# Input.net
KiCad netlist of a schematic drawn in Altium Designer
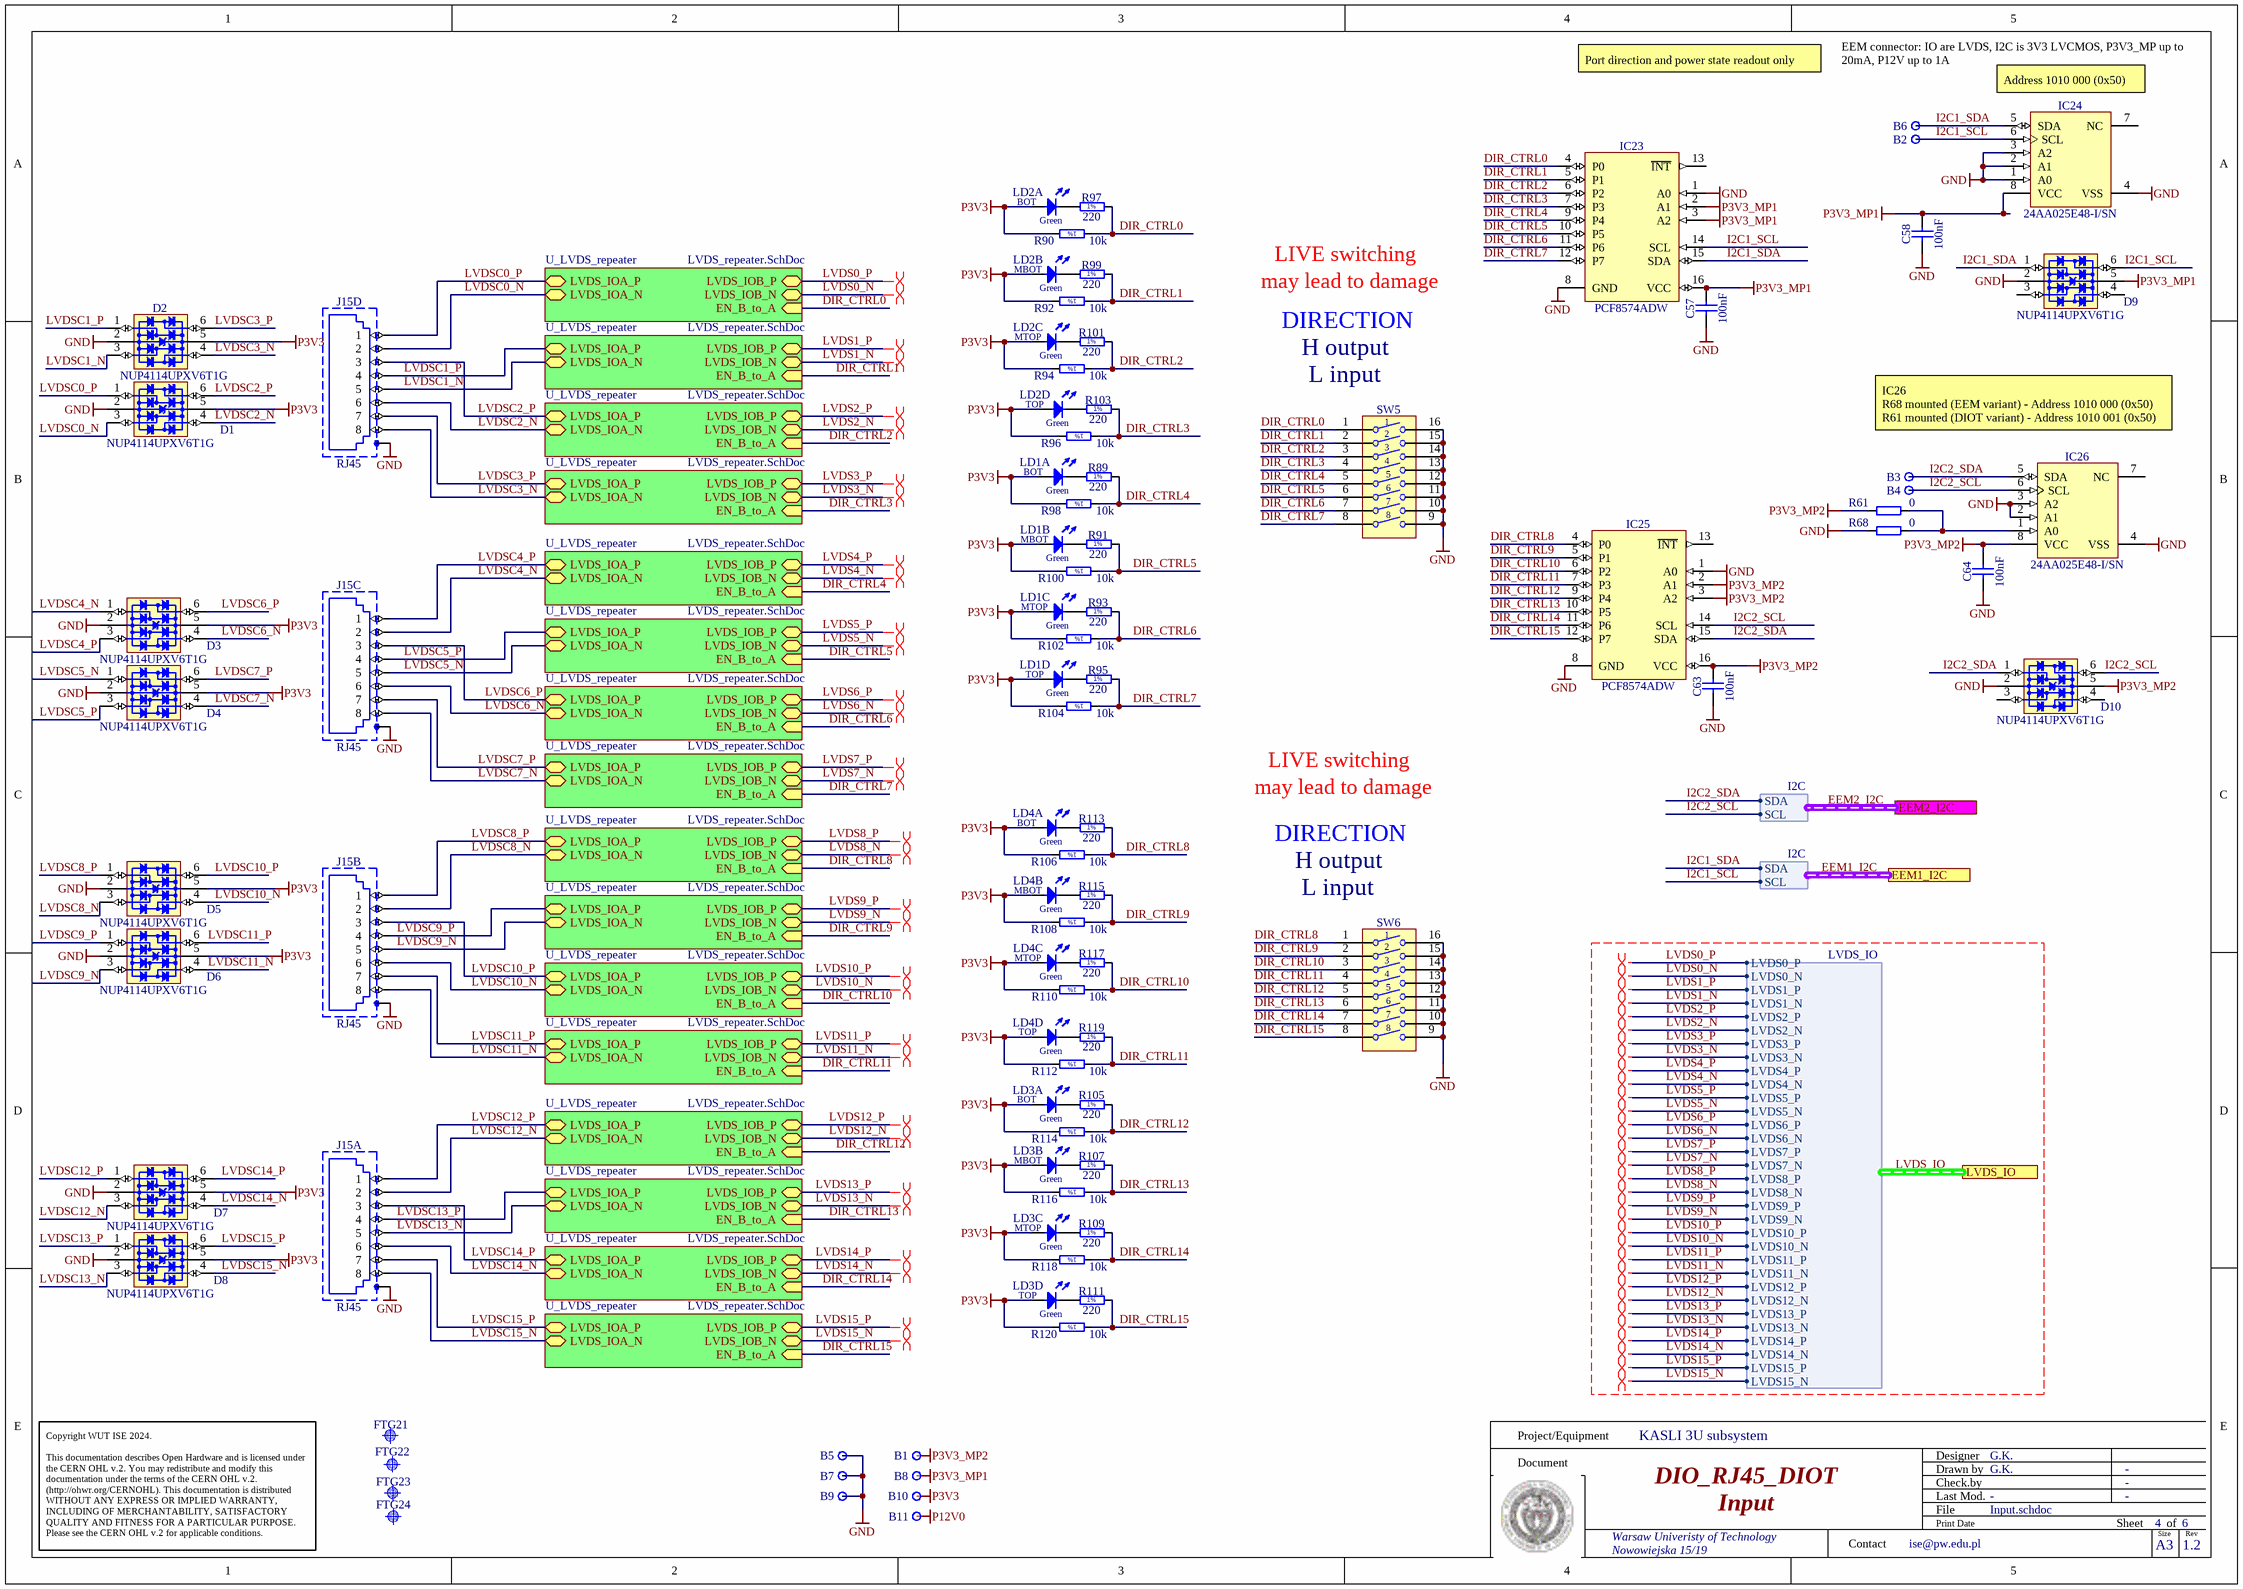
[diagram p0: Input.schdoc]

(export (version "E")
  (design (tool "Eeschema 10.0.6"))
  (components
    (comp (ref "B1")
      (value "Plated Hole")
      (footprint "c130h60")
      (description "Single Terminal Socket")
      (fields (field (name "PART NUMBER") "PLATED_HOLE0.6_PAD1.3") (field (name "AUTHOR") "CERN DEM MR"))
      (libsource (lib "Eletro-mechanical") (part "Single Terminal Socket"))
    )
    (comp (ref "B2")
      (value "Plated Hole")
      (footprint "c130h60")
      (description "Single Terminal Socket")
      (fields (field (name "PART NUMBER") "PLATED_HOLE0.6_PAD1.3") (field (name "AUTHOR") "CERN DEM MR"))
      (libsource (lib "Eletro-mechanical") (part "Single Terminal Socket"))
    )
    (comp (ref "B3")
      (value "Plated Hole")
      (footprint "c130h60")
      (description "Single Terminal Socket")
      (fields (field (name "PART NUMBER") "PLATED_HOLE0.6_PAD1.3") (field (name "AUTHOR") "CERN DEM MR"))
      (libsource (lib "Eletro-mechanical") (part "Single Terminal Socket"))
    )
    (comp (ref "B4")
      (value "Plated Hole")
      (footprint "c130h60")
      (description "Single Terminal Socket")
      (fields (field (name "PART NUMBER") "PLATED_HOLE0.6_PAD1.3") (field (name "AUTHOR") "CERN DEM MR"))
      (libsource (lib "Eletro-mechanical") (part "Single Terminal Socket"))
    )
    (comp (ref "B5")
      (value "Plated Hole")
      (footprint "c130h60")
      (description "Single Terminal Socket")
      (fields (field (name "PART NUMBER") "PLATED_HOLE0.6_PAD1.3") (field (name "AUTHOR") "CERN DEM MR"))
      (libsource (lib "Eletro-mechanical") (part "Single Terminal Socket"))
    )
    (comp (ref "B6")
      (value "Plated Hole")
      (footprint "c130h60")
      (description "Single Terminal Socket")
      (fields (field (name "PART NUMBER") "PLATED_HOLE0.6_PAD1.3") (field (name "AUTHOR") "CERN DEM MR"))
      (libsource (lib "Eletro-mechanical") (part "Single Terminal Socket"))
    )
    (comp (ref "B7")
      (value "Plated Hole")
      (footprint "c130h60")
      (description "Single Terminal Socket")
      (fields (field (name "PART NUMBER") "PLATED_HOLE0.6_PAD1.3") (field (name "AUTHOR") "CERN DEM MR"))
      (libsource (lib "Eletro-mechanical") (part "Single Terminal Socket"))
    )
    (comp (ref "B8")
      (value "Plated Hole")
      (footprint "c130h60")
      (description "Single Terminal Socket")
      (fields (field (name "PART NUMBER") "PLATED_HOLE0.6_PAD1.3") (field (name "AUTHOR") "CERN DEM MR"))
      (libsource (lib "Eletro-mechanical") (part "Single Terminal Socket"))
    )
    (comp (ref "B9")
      (value "Plated Hole")
      (footprint "c130h60")
      (description "Single Terminal Socket")
      (fields (field (name "PART NUMBER") "PLATED_HOLE0.6_PAD1.3") (field (name "AUTHOR") "CERN DEM MR"))
      (libsource (lib "Eletro-mechanical") (part "Single Terminal Socket"))
    )
    (comp (ref "B10")
      (value "Plated Hole")
      (footprint "c130h60")
      (description "Single Terminal Socket")
      (fields (field (name "PART NUMBER") "PLATED_HOLE0.6_PAD1.3") (field (name "AUTHOR") "CERN DEM MR"))
      (libsource (lib "Eletro-mechanical") (part "Single Terminal Socket"))
    )
    (comp (ref "B11")
      (value "Plated Hole")
      (footprint "c130h60")
      (description "Single Terminal Socket")
      (fields (field (name "PART NUMBER") "PLATED_HOLE0.6_PAD1.3") (field (name "AUTHOR") "CERN DEM MR"))
      (libsource (lib "Eletro-mechanical") (part "Single Terminal Socket"))
    )
    (comp (ref "C57")
      (value "100nF")
      (footprint "CAPC1005X55N")
      (description "Non-polarised capacitor")
      (fields
        (field (name "PART NUMBER") "CC0402_100NF_16V_10%_X5R")
        (field (name "VOLTAGE") "16V")
        (field (name "AUTHOR") "CERN DEM JLC")
      )
      (libsource (lib "Capacitors") (part "Capacitor - non polarized"))
    )
    (comp (ref "C58")
      (value "100nF")
      (footprint "CAPC1005X55N")
      (description "Non-polarised capacitor")
      (fields
        (field (name "PART NUMBER") "CC0402_100NF_16V_10%_X5R")
        (field (name "VOLTAGE") "16V")
        (field (name "AUTHOR") "CERN DEM JLC")
      )
      (libsource (lib "Capacitors") (part "Capacitor - non polarized"))
    )
    (comp (ref "C63")
      (value "100nF")
      (footprint "CAPC1005X55N")
      (description "Non-polarised capacitor")
      (fields
        (field (name "PART NUMBER") "CC0402_100NF_16V_10%_X5R")
        (field (name "VOLTAGE") "16V")
        (field (name "AUTHOR") "CERN DEM JLC")
      )
      (libsource (lib "Capacitors") (part "Capacitor - non polarized"))
    )
    (comp (ref "C64")
      (value "100nF")
      (footprint "CAPC1005X55N")
      (description "Non-polarised capacitor")
      (fields
        (field (name "PART NUMBER") "CC0402_100NF_16V_10%_X5R")
        (field (name "VOLTAGE") "16V")
        (field (name "AUTHOR") "CERN DEM JLC")
      )
      (libsource (lib "Capacitors") (part "Capacitor - non polarized"))
    )
    (comp (ref "D1")
      (value "NUP4114UPXV6T1G")
      (footprint "SOTFL50P160X60-6N")
      (fields
        (field (name "VOLTAGE") "5.5V")
        (field (name "MANUFACTURER") "ON SEMICONDUCTOR")
        (field (name "AUTHOR") "CERN DEM JLC")
      )
      (libsource (lib "ICs And Semiconductors") (part "NUP4114"))
    )
    (comp (ref "D2")
      (value "NUP4114UPXV6T1G")
      (footprint "SOTFL50P160X60-6N")
      (fields
        (field (name "VOLTAGE") "5.5V")
        (field (name "MANUFACTURER") "ON SEMICONDUCTOR")
        (field (name "AUTHOR") "CERN DEM JLC")
      )
      (libsource (lib "ICs And Semiconductors") (part "NUP4114"))
    )
    (comp (ref "D3")
      (value "NUP4114UPXV6T1G")
      (footprint "SOTFL50P160X60-6N")
      (fields
        (field (name "VOLTAGE") "5.5V")
        (field (name "MANUFACTURER") "ON SEMICONDUCTOR")
        (field (name "AUTHOR") "CERN DEM JLC")
      )
      (libsource (lib "ICs And Semiconductors") (part "NUP4114"))
    )
    (comp (ref "D4")
      (value "NUP4114UPXV6T1G")
      (footprint "SOTFL50P160X60-6N")
      (fields
        (field (name "VOLTAGE") "5.5V")
        (field (name "MANUFACTURER") "ON SEMICONDUCTOR")
        (field (name "AUTHOR") "CERN DEM JLC")
      )
      (libsource (lib "ICs And Semiconductors") (part "NUP4114"))
    )
    (comp (ref "D5")
      (value "NUP4114UPXV6T1G")
      (footprint "SOTFL50P160X60-6N")
      (fields
        (field (name "VOLTAGE") "5.5V")
        (field (name "MANUFACTURER") "ON SEMICONDUCTOR")
        (field (name "AUTHOR") "CERN DEM JLC")
      )
      (libsource (lib "ICs And Semiconductors") (part "NUP4114"))
    )
    (comp (ref "D6")
      (value "NUP4114UPXV6T1G")
      (footprint "SOTFL50P160X60-6N")
      (fields
        (field (name "VOLTAGE") "5.5V")
        (field (name "MANUFACTURER") "ON SEMICONDUCTOR")
        (field (name "AUTHOR") "CERN DEM JLC")
      )
      (libsource (lib "ICs And Semiconductors") (part "NUP4114"))
    )
    (comp (ref "D7")
      (value "NUP4114UPXV6T1G")
      (footprint "SOTFL50P160X60-6N")
      (fields
        (field (name "VOLTAGE") "5.5V")
        (field (name "MANUFACTURER") "ON SEMICONDUCTOR")
        (field (name "AUTHOR") "CERN DEM JLC")
      )
      (libsource (lib "ICs And Semiconductors") (part "NUP4114"))
    )
    (comp (ref "D8")
      (value "NUP4114UPXV6T1G")
      (footprint "SOTFL50P160X60-6N")
      (fields
        (field (name "VOLTAGE") "5.5V")
        (field (name "MANUFACTURER") "ON SEMICONDUCTOR")
        (field (name "AUTHOR") "CERN DEM JLC")
      )
      (libsource (lib "ICs And Semiconductors") (part "NUP4114"))
    )
    (comp (ref "D9")
      (value "NUP4114UPXV6T1G")
      (footprint "SOTFL50P160X60-6N")
      (fields
        (field (name "VOLTAGE") "5.5V")
        (field (name "MANUFACTURER") "ON SEMICONDUCTOR")
        (field (name "AUTHOR") "CERN DEM JLC")
      )
      (libsource (lib "ICs And Semiconductors") (part "NUP4114"))
    )
    (comp (ref "D10")
      (value "NUP4114UPXV6T1G")
      (footprint "SOTFL50P160X60-6N")
      (fields
        (field (name "VOLTAGE") "5.5V")
        (field (name "MANUFACTURER") "ON SEMICONDUCTOR")
        (field (name "AUTHOR") "CERN DEM JLC")
      )
      (libsource (lib "ICs And Semiconductors") (part "NUP4114"))
    )
    (comp (ref "FTG21")
      (value "Use only in PCB")
      (footprint "FIDUCIAL_TOP_C100-200")
      (description "Fiducial Target")
      (fields (field (name "PART NUMBER") "FIDUCIAL_TARGET_C100-200") (field (name "AUTHOR") "CERN DEM JLC"))
      (libsource (lib "Eletro-mechanical") (part "Fiducial Target"))
    )
    (comp (ref "FTG22")
      (value "Use only in PCB")
      (footprint "FIDUCIAL_TOP_S100-200")
      (description "Fiducial Target")
      (fields (field (name "PART NUMBER") "FIDUCIAL_TARGET_S100-200") (field (name "AUTHOR") "CERN DEM JLC"))
      (libsource (lib "Eletro-mechanical") (part "Fiducial Target"))
    )
    (comp (ref "FTG23")
      (value "Use only in PCB")
      (footprint "FIDUCIAL_TOP_S200-400")
      (description "Fiducial Target")
      (fields (field (name "PART NUMBER") "FIDUCIAL_TARGET_S200-400") (field (name "AUTHOR") "CERN DEM JLC"))
      (libsource (lib "Eletro-mechanical") (part "Fiducial Target"))
    )
    (comp (ref "FTG24")
      (value "Use only in PCB")
      (footprint "FIDUCIAL_TOP_S100-200")
      (description "Fiducial Target")
      (fields (field (name "PART NUMBER") "FIDUCIAL_TARGET_S100-200") (field (name "AUTHOR") "CERN DEM JLC"))
      (libsource (lib "Eletro-mechanical") (part "Fiducial Target"))
    )
    (comp (ref "IC23")
      (value "PCF8574ADW")
      (footprint "SOIC127P1030X265-16N")
      (description "Remote 8-bit I/O Expander For I2C Bus")
      (fields (field (name "MANUFACTURER") "TEXAS INSTRUMENTS") (field (name "AUTHOR") "CERN DEM JLC"))
      (libsource (lib "ICs And Semiconductors") (part "PCF8574ADW"))
    )
    (comp (ref "IC24")
      (value "24AA025E48-I/SN")
      (footprint "SOIC127P600X175-8N")
      (description "1.7V-5.5V, 2K I2C™ Serial EEPROMs with EUI-48™ Node Identity")
      (fields (field (name "MANUFACTURER") "MICROCHIP TECHNOLOGY") (field (name "AUTHOR") "CERN DEM MR"))
      (libsource (lib "ICs And Semiconductors") (part "24AA025E48-I/SN"))
    )
    (comp (ref "IC25")
      (value "PCF8574ADW")
      (footprint "SOIC127P1030X265-16N")
      (description "Remote 8-bit I/O Expander For I2C Bus")
      (fields (field (name "MANUFACTURER") "TEXAS INSTRUMENTS") (field (name "AUTHOR") "CERN DEM JLC"))
      (libsource (lib "ICs And Semiconductors") (part "PCF8574ADW"))
    )
    (comp (ref "IC26")
      (value "24AA025E48-I/SN")
      (footprint "SOIC127P600X175-8N")
      (description "1.7V-5.5V, 2K I2C™ Serial EEPROMs with EUI-48™ Node Identity")
      (fields (field (name "MANUFACTURER") "MICROCHIP TECHNOLOGY") (field (name "AUTHOR") "CERN DEM MR"))
      (libsource (lib "ICs And Semiconductors") (part "24AA025E48-I/SN"))
    )
    (comp (ref "J15")
      (value "RJ45")
      (footprint "TYCO_5406203-3")
      (description "Connector 4 x RJ45 + Shield")
      (fields
        (field (name "PART NUMBER") "TYCO_5406203-3")
        (field (name "MANUFACTURER") "TYCO ELECTRONICS")
        (field (name "AUTHOR") "CERN DEM JLC")
      )
      (libsource (lib "Connectors") (part "Connector 4 x RJ45 + Shield"))
    )
    (comp (ref "LD1")
      (value "Green")
      (footprint "LED_BIVAR_H485CGDL")
      (description "LED x4 Green 1C2A-BOT_3C4A_5C6A_7C8A-TOP")
      (fields
        (field (name "PART NUMBER") "LED_BIVAR_H485CGDL")
        (field (name "MANUFACTURER") "BIVAR")
        (field (name "AUTHOR") "CERN DEM JLC")
      )
      (libsource (lib "ICs And Semiconductors") (part "LED x4 Green 1C2A-BOT_3C4A_5C6A_7C8A-TOP"))
    )
    (comp (ref "LD2")
      (value "Green")
      (footprint "LED_BIVAR_H485CGDL")
      (description "LED x4 Green 1C2A-BOT_3C4A_5C6A_7C8A-TOP")
      (fields
        (field (name "PART NUMBER") "LED_BIVAR_H485CGDL")
        (field (name "MANUFACTURER") "BIVAR")
        (field (name "AUTHOR") "CERN DEM JLC")
      )
      (libsource (lib "ICs And Semiconductors") (part "LED x4 Green 1C2A-BOT_3C4A_5C6A_7C8A-TOP"))
    )
    (comp (ref "LD3")
      (value "Green")
      (footprint "LED_BIVAR_H485CGDL")
      (description "LED x4 Green 1C2A-BOT_3C4A_5C6A_7C8A-TOP")
      (fields
        (field (name "PART NUMBER") "LED_BIVAR_H485CGDL")
        (field (name "MANUFACTURER") "BIVAR")
        (field (name "AUTHOR") "CERN DEM JLC")
      )
      (libsource (lib "ICs And Semiconductors") (part "LED x4 Green 1C2A-BOT_3C4A_5C6A_7C8A-TOP"))
    )
    (comp (ref "LD4")
      (value "Green")
      (footprint "LED_BIVAR_H485CGDL")
      (description "LED x4 Green 1C2A-BOT_3C4A_5C6A_7C8A-TOP")
      (fields
        (field (name "PART NUMBER") "LED_BIVAR_H485CGDL")
        (field (name "MANUFACTURER") "BIVAR")
        (field (name "AUTHOR") "CERN DEM JLC")
      )
      (libsource (lib "ICs And Semiconductors") (part "LED x4 Green 1C2A-BOT_3C4A_5C6A_7C8A-TOP"))
    )
    (comp (ref "R61")
      (value "0")
      (footprint "RESC1005X35N")
      (description "Resistor")
      (fields
        (field (name "PART NUMBER") "R0402_0R_JUMPER")
        (field (name "MANUFACTURER") "GENERIC")
        (field (name "AUTHOR") "CERN DEM JLC")
      )
      (libsource (lib "Resistors") (part "Resistor"))
    )
    (comp (ref "R68")
      (value "0")
      (footprint "RESC1005X35N")
      (description "Resistor")
      (fields
        (field (name "PART NUMBER") "R0402_0R_JUMPER")
        (field (name "MANUFACTURER") "GENERIC")
        (field (name "AUTHOR") "CERN DEM JLC")
      )
      (libsource (lib "Resistors") (part "Resistor"))
    )
    (comp (ref "R89")
      (value "220")
      (footprint "RESC1608X55N")
      (description "Resistor - 1%")
      (fields
        (field (name "PART NUMBER") "R0603_220R_1%_0.1W_100PPM")
        (field (name "POWER") "0.1W")
        (field (name "AUTHOR") "CERN DEM JLC")
      )
      (libsource (lib "Resistors") (part "Resistor - 1%"))
    )
    (comp (ref "R90")
      (value "10k")
      (footprint "RESC1005X40N")
      (description "Resistor - 1%")
      (fields
        (field (name "PART NUMBER") "R0402_10K_1%_0.0625W_100PPM")
        (field (name "POWER") "0.0625W")
        (field (name "AUTHOR") "CERN DEM JLC")
      )
      (libsource (lib "Resistors") (part "Resistor - 1%"))
    )
    (comp (ref "R91")
      (value "220")
      (footprint "RESC1608X55N")
      (description "Resistor - 1%")
      (fields
        (field (name "PART NUMBER") "R0603_220R_1%_0.1W_100PPM")
        (field (name "POWER") "0.1W")
        (field (name "AUTHOR") "CERN DEM JLC")
      )
      (libsource (lib "Resistors") (part "Resistor - 1%"))
    )
    (comp (ref "R92")
      (value "10k")
      (footprint "RESC1005X40N")
      (description "Resistor - 1%")
      (fields
        (field (name "PART NUMBER") "R0402_10K_1%_0.0625W_100PPM")
        (field (name "POWER") "0.0625W")
        (field (name "AUTHOR") "CERN DEM JLC")
      )
      (libsource (lib "Resistors") (part "Resistor - 1%"))
    )
    (comp (ref "R93")
      (value "220")
      (footprint "RESC1608X55N")
      (description "Resistor - 1%")
      (fields
        (field (name "PART NUMBER") "R0603_220R_1%_0.1W_100PPM")
        (field (name "POWER") "0.1W")
        (field (name "AUTHOR") "CERN DEM JLC")
      )
      (libsource (lib "Resistors") (part "Resistor - 1%"))
    )
    (comp (ref "R94")
      (value "10k")
      (footprint "RESC1005X40N")
      (description "Resistor - 1%")
      (fields
        (field (name "PART NUMBER") "R0402_10K_1%_0.0625W_100PPM")
        (field (name "POWER") "0.0625W")
        (field (name "AUTHOR") "CERN DEM JLC")
      )
      (libsource (lib "Resistors") (part "Resistor - 1%"))
    )
    (comp (ref "R95")
      (value "220")
      (footprint "RESC1608X55N")
      (description "Resistor - 1%")
      (fields
        (field (name "PART NUMBER") "R0603_220R_1%_0.1W_100PPM")
        (field (name "POWER") "0.1W")
        (field (name "AUTHOR") "CERN DEM JLC")
      )
      (libsource (lib "Resistors") (part "Resistor - 1%"))
    )
    (comp (ref "R96")
      (value "10k")
      (footprint "RESC1005X40N")
      (description "Resistor - 1%")
      (fields
        (field (name "PART NUMBER") "R0402_10K_1%_0.0625W_100PPM")
        (field (name "POWER") "0.0625W")
        (field (name "AUTHOR") "CERN DEM JLC")
      )
      (libsource (lib "Resistors") (part "Resistor - 1%"))
    )
    (comp (ref "R97")
      (value "220")
      (footprint "RESC1608X55N")
      (description "Resistor - 1%")
      (fields
        (field (name "PART NUMBER") "R0603_220R_1%_0.1W_100PPM")
        (field (name "POWER") "0.1W")
        (field (name "AUTHOR") "CERN DEM JLC")
      )
      (libsource (lib "Resistors") (part "Resistor - 1%"))
    )
    (comp (ref "R98")
      (value "10k")
      (footprint "RESC1005X40N")
      (description "Resistor - 1%")
      (fields
        (field (name "PART NUMBER") "R0402_10K_1%_0.0625W_100PPM")
        (field (name "POWER") "0.0625W")
        (field (name "AUTHOR") "CERN DEM JLC")
      )
      (libsource (lib "Resistors") (part "Resistor - 1%"))
    )
    (comp (ref "R99")
      (value "220")
      (footprint "RESC1608X55N")
      (description "Resistor - 1%")
      (fields
        (field (name "PART NUMBER") "R0603_220R_1%_0.1W_100PPM")
        (field (name "POWER") "0.1W")
        (field (name "AUTHOR") "CERN DEM JLC")
      )
      (libsource (lib "Resistors") (part "Resistor - 1%"))
    )
    (comp (ref "R100")
      (value "10k")
      (footprint "RESC1005X40N")
      (description "Resistor - 1%")
      (fields
        (field (name "PART NUMBER") "R0402_10K_1%_0.0625W_100PPM")
        (field (name "POWER") "0.0625W")
        (field (name "AUTHOR") "CERN DEM JLC")
      )
      (libsource (lib "Resistors") (part "Resistor - 1%"))
    )
    (comp (ref "R101")
      (value "220")
      (footprint "RESC1608X55N")
      (description "Resistor - 1%")
      (fields
        (field (name "PART NUMBER") "R0603_220R_1%_0.1W_100PPM")
        (field (name "POWER") "0.1W")
        (field (name "AUTHOR") "CERN DEM JLC")
      )
      (libsource (lib "Resistors") (part "Resistor - 1%"))
    )
    (comp (ref "R102")
      (value "10k")
      (footprint "RESC1005X40N")
      (description "Resistor - 1%")
      (fields
        (field (name "PART NUMBER") "R0402_10K_1%_0.0625W_100PPM")
        (field (name "POWER") "0.0625W")
        (field (name "AUTHOR") "CERN DEM JLC")
      )
      (libsource (lib "Resistors") (part "Resistor - 1%"))
    )
    (comp (ref "R103")
      (value "220")
      (footprint "RESC1608X55N")
      (description "Resistor - 1%")
      (fields
        (field (name "PART NUMBER") "R0603_220R_1%_0.1W_100PPM")
        (field (name "POWER") "0.1W")
        (field (name "AUTHOR") "CERN DEM JLC")
      )
      (libsource (lib "Resistors") (part "Resistor - 1%"))
    )
    (comp (ref "R104")
      (value "10k")
      (footprint "RESC1005X40N")
      (description "Resistor - 1%")
      (fields
        (field (name "PART NUMBER") "R0402_10K_1%_0.0625W_100PPM")
        (field (name "POWER") "0.0625W")
        (field (name "AUTHOR") "CERN DEM JLC")
      )
      (libsource (lib "Resistors") (part "Resistor - 1%"))
    )
    (comp (ref "R105")
      (value "220")
      (footprint "RESC1608X55N")
      (description "Resistor - 1%")
      (fields
        (field (name "PART NUMBER") "R0603_220R_1%_0.1W_100PPM")
        (field (name "POWER") "0.1W")
        (field (name "AUTHOR") "CERN DEM JLC")
      )
      (libsource (lib "Resistors") (part "Resistor - 1%"))
    )
    (comp (ref "R106")
      (value "10k")
      (footprint "RESC1005X40N")
      (description "Resistor - 1%")
      (fields
        (field (name "PART NUMBER") "R0402_10K_1%_0.0625W_100PPM")
        (field (name "POWER") "0.0625W")
        (field (name "AUTHOR") "CERN DEM JLC")
      )
      (libsource (lib "Resistors") (part "Resistor - 1%"))
    )
    (comp (ref "R107")
      (value "220")
      (footprint "RESC1608X55N")
      (description "Resistor - 1%")
      (fields
        (field (name "PART NUMBER") "R0603_220R_1%_0.1W_100PPM")
        (field (name "POWER") "0.1W")
        (field (name "AUTHOR") "CERN DEM JLC")
      )
      (libsource (lib "Resistors") (part "Resistor - 1%"))
    )
    (comp (ref "R108")
      (value "10k")
      (footprint "RESC1005X40N")
      (description "Resistor - 1%")
      (fields
        (field (name "PART NUMBER") "R0402_10K_1%_0.0625W_100PPM")
        (field (name "POWER") "0.0625W")
        (field (name "AUTHOR") "CERN DEM JLC")
      )
      (libsource (lib "Resistors") (part "Resistor - 1%"))
    )
    (comp (ref "R109")
      (value "220")
      (footprint "RESC1608X55N")
      (description "Resistor - 1%")
      (fields
        (field (name "PART NUMBER") "R0603_220R_1%_0.1W_100PPM")
        (field (name "POWER") "0.1W")
        (field (name "AUTHOR") "CERN DEM JLC")
      )
      (libsource (lib "Resistors") (part "Resistor - 1%"))
    )
    (comp (ref "R110")
      (value "10k")
      (footprint "RESC1005X40N")
      (description "Resistor - 1%")
      (fields
        (field (name "PART NUMBER") "R0402_10K_1%_0.0625W_100PPM")
        (field (name "POWER") "0.0625W")
        (field (name "AUTHOR") "CERN DEM JLC")
      )
      (libsource (lib "Resistors") (part "Resistor - 1%"))
    )
    (comp (ref "R111")
      (value "220")
      (footprint "RESC1608X55N")
      (description "Resistor - 1%")
      (fields
        (field (name "PART NUMBER") "R0603_220R_1%_0.1W_100PPM")
        (field (name "POWER") "0.1W")
        (field (name "AUTHOR") "CERN DEM JLC")
      )
      (libsource (lib "Resistors") (part "Resistor - 1%"))
    )
    (comp (ref "R112")
      (value "10k")
      (footprint "RESC1005X40N")
      (description "Resistor - 1%")
      (fields
        (field (name "PART NUMBER") "R0402_10K_1%_0.0625W_100PPM")
        (field (name "POWER") "0.0625W")
        (field (name "AUTHOR") "CERN DEM JLC")
      )
      (libsource (lib "Resistors") (part "Resistor - 1%"))
    )
    (comp (ref "R113")
      (value "220")
      (footprint "RESC1608X55N")
      (description "Resistor - 1%")
      (fields
        (field (name "PART NUMBER") "R0603_220R_1%_0.1W_100PPM")
        (field (name "POWER") "0.1W")
        (field (name "AUTHOR") "CERN DEM JLC")
      )
      (libsource (lib "Resistors") (part "Resistor - 1%"))
    )
    (comp (ref "R114")
      (value "10k")
      (footprint "RESC1005X40N")
      (description "Resistor - 1%")
      (fields
        (field (name "PART NUMBER") "R0402_10K_1%_0.0625W_100PPM")
        (field (name "POWER") "0.0625W")
        (field (name "AUTHOR") "CERN DEM JLC")
      )
      (libsource (lib "Resistors") (part "Resistor - 1%"))
    )
    (comp (ref "R115")
      (value "220")
      (footprint "RESC1608X55N")
      (description "Resistor - 1%")
      (fields
        (field (name "PART NUMBER") "R0603_220R_1%_0.1W_100PPM")
        (field (name "POWER") "0.1W")
        (field (name "AUTHOR") "CERN DEM JLC")
      )
      (libsource (lib "Resistors") (part "Resistor - 1%"))
    )
    (comp (ref "R116")
      (value "10k")
      (footprint "RESC1005X40N")
      (description "Resistor - 1%")
      (fields
        (field (name "PART NUMBER") "R0402_10K_1%_0.0625W_100PPM")
        (field (name "POWER") "0.0625W")
        (field (name "AUTHOR") "CERN DEM JLC")
      )
      (libsource (lib "Resistors") (part "Resistor - 1%"))
    )
    (comp (ref "R117")
      (value "220")
      (footprint "RESC1608X55N")
      (description "Resistor - 1%")
      (fields
        (field (name "PART NUMBER") "R0603_220R_1%_0.1W_100PPM")
        (field (name "POWER") "0.1W")
        (field (name "AUTHOR") "CERN DEM JLC")
      )
      (libsource (lib "Resistors") (part "Resistor - 1%"))
    )
    (comp (ref "R118")
      (value "10k")
      (footprint "RESC1005X40N")
      (description "Resistor - 1%")
      (fields
        (field (name "PART NUMBER") "R0402_10K_1%_0.0625W_100PPM")
        (field (name "POWER") "0.0625W")
        (field (name "AUTHOR") "CERN DEM JLC")
      )
      (libsource (lib "Resistors") (part "Resistor - 1%"))
    )
    (comp (ref "R119")
      (value "220")
      (footprint "RESC1608X55N")
      (description "Resistor - 1%")
      (fields
        (field (name "PART NUMBER") "R0603_220R_1%_0.1W_100PPM")
        (field (name "POWER") "0.1W")
        (field (name "AUTHOR") "CERN DEM JLC")
      )
      (libsource (lib "Resistors") (part "Resistor - 1%"))
    )
    (comp (ref "R120")
      (value "10k")
      (footprint "RESC1005X40N")
      (description "Resistor - 1%")
      (fields
        (field (name "PART NUMBER") "R0402_10K_1%_0.0625W_100PPM")
        (field (name "POWER") "0.0625W")
        (field (name "AUTHOR") "CERN DEM JLC")
      )
      (libsource (lib "Resistors") (part "Resistor - 1%"))
    )
    (comp (ref "SW5")
      (value "Switch")
      (footprint "SW_TYCO_1-1571983-0")
      (description "8 Ways SPST DIP Switch")
      (fields
        (field (name "PART NUMBER") "SW_TYCO_1-1571983-0")
        (field (name "MANUFACTURER") "TYCO")
        (field (name "AUTHOR") "CERN DEM JLC")
      )
      (libsource (lib "Eletro-mechanical") (part "SW 8x SPST DIP Switch"))
    )
    (comp (ref "SW6")
      (value "Switch")
      (footprint "SW_TYCO_1-1571983-0")
      (description "8 Ways SPST DIP Switch")
      (fields
        (field (name "PART NUMBER") "SW_TYCO_1-1571983-0")
        (field (name "MANUFACTURER") "TYCO")
        (field (name "AUTHOR") "CERN DEM JLC")
      )
      (libsource (lib "Eletro-mechanical") (part "SW 8x SPST DIP Switch"))
    )
  )
  (nets
    (net (code "4") (name "/DIR_CTRL0") (class "Default")
      (node (ref "IC23") (pin "4") (pinfunction "P0_4") (pintype "bidirectional"))
      (node (ref "R90") (pin "1") (pinfunction "1_1") (pintype "passive"))
      (node (ref "R97") (pin "2") (pinfunction "2_2") (pintype "passive"))
      (node (ref "SW5") (pin "1") (pinfunction "1_1") (pintype "passive"))
    )
    (net (code "5") (name "/DIR_CTRL1") (class "Default")
      (node (ref "IC23") (pin "5") (pinfunction "P1_5") (pintype "bidirectional"))
      (node (ref "R92") (pin "1") (pinfunction "1_1") (pintype "passive"))
      (node (ref "R99") (pin "2") (pinfunction "2_2") (pintype "passive"))
      (node (ref "SW5") (pin "2") (pinfunction "2_2") (pintype "passive"))
    )
    (net (code "6") (name "/DIR_CTRL2") (class "Default")
      (node (ref "IC23") (pin "6") (pinfunction "P2_6") (pintype "bidirectional"))
      (node (ref "R101") (pin "2") (pinfunction "2_2") (pintype "passive"))
      (node (ref "R94") (pin "1") (pinfunction "1_1") (pintype "passive"))
      (node (ref "SW5") (pin "3") (pinfunction "3_3") (pintype "passive"))
    )
    (net (code "7") (name "/DIR_CTRL3") (class "Default")
      (node (ref "IC23") (pin "7") (pinfunction "P3_7") (pintype "bidirectional"))
      (node (ref "R103") (pin "2") (pinfunction "2_2") (pintype "passive"))
      (node (ref "R96") (pin "1") (pinfunction "1_1") (pintype "passive"))
      (node (ref "SW5") (pin "4") (pinfunction "4_4") (pintype "passive"))
    )
    (net (code "8") (name "/DIR_CTRL4") (class "Default")
      (node (ref "IC23") (pin "9") (pinfunction "P4_9") (pintype "bidirectional"))
      (node (ref "R89") (pin "2") (pinfunction "2_2") (pintype "passive"))
      (node (ref "R98") (pin "1") (pinfunction "1_1") (pintype "passive"))
      (node (ref "SW5") (pin "5") (pinfunction "5_5") (pintype "passive"))
    )
    (net (code "9") (name "/DIR_CTRL5") (class "Default")
      (node (ref "IC23") (pin "10") (pinfunction "P5_10") (pintype "bidirectional"))
      (node (ref "R100") (pin "1") (pinfunction "1_1") (pintype "passive"))
      (node (ref "R91") (pin "2") (pinfunction "2_2") (pintype "passive"))
      (node (ref "SW5") (pin "6") (pinfunction "6_6") (pintype "passive"))
    )
    (net (code "10") (name "/DIR_CTRL6") (class "Default")
      (node (ref "IC23") (pin "11") (pinfunction "P6_11") (pintype "bidirectional"))
      (node (ref "R102") (pin "1") (pinfunction "1_1") (pintype "passive"))
      (node (ref "R93") (pin "2") (pinfunction "2_2") (pintype "passive"))
      (node (ref "SW5") (pin "7") (pinfunction "7_7") (pintype "passive"))
    )
    (net (code "11") (name "/DIR_CTRL7") (class "Default")
      (node (ref "IC23") (pin "12") (pinfunction "P7_12") (pintype "bidirectional"))
      (node (ref "R104") (pin "1") (pinfunction "1_1") (pintype "passive"))
      (node (ref "R95") (pin "2") (pinfunction "2_2") (pintype "passive"))
      (node (ref "SW5") (pin "8") (pinfunction "8_8") (pintype "passive"))
    )
    (net (code "12") (name "/DIR_CTRL8") (class "Default")
      (node (ref "IC25") (pin "4") (pinfunction "P0_4") (pintype "bidirectional"))
      (node (ref "R106") (pin "1") (pinfunction "1_1") (pintype "passive"))
      (node (ref "R113") (pin "2") (pinfunction "2_2") (pintype "passive"))
      (node (ref "SW6") (pin "1") (pinfunction "1_1") (pintype "passive"))
    )
    (net (code "13") (name "/DIR_CTRL9") (class "Default")
      (node (ref "IC25") (pin "5") (pinfunction "P1_5") (pintype "bidirectional"))
      (node (ref "R108") (pin "1") (pinfunction "1_1") (pintype "passive"))
      (node (ref "R115") (pin "2") (pinfunction "2_2") (pintype "passive"))
      (node (ref "SW6") (pin "2") (pinfunction "2_2") (pintype "passive"))
    )
    (net (code "14") (name "/DIR_CTRL10") (class "Default")
      (node (ref "IC25") (pin "6") (pinfunction "P2_6") (pintype "bidirectional"))
      (node (ref "R110") (pin "1") (pinfunction "1_1") (pintype "passive"))
      (node (ref "R117") (pin "2") (pinfunction "2_2") (pintype "passive"))
      (node (ref "SW6") (pin "3") (pinfunction "3_3") (pintype "passive"))
    )
    (net (code "15") (name "/DIR_CTRL11") (class "Default")
      (node (ref "IC25") (pin "7") (pinfunction "P3_7") (pintype "bidirectional"))
      (node (ref "R112") (pin "1") (pinfunction "1_1") (pintype "passive"))
      (node (ref "R119") (pin "2") (pinfunction "2_2") (pintype "passive"))
      (node (ref "SW6") (pin "4") (pinfunction "4_4") (pintype "passive"))
    )
    (net (code "16") (name "/DIR_CTRL12") (class "Default")
      (node (ref "IC25") (pin "9") (pinfunction "P4_9") (pintype "bidirectional"))
      (node (ref "R105") (pin "2") (pinfunction "2_2") (pintype "passive"))
      (node (ref "R114") (pin "1") (pinfunction "1_1") (pintype "passive"))
      (node (ref "SW6") (pin "5") (pinfunction "5_5") (pintype "passive"))
    )
    (net (code "17") (name "/DIR_CTRL13") (class "Default")
      (node (ref "IC25") (pin "10") (pinfunction "P5_10") (pintype "bidirectional"))
      (node (ref "R107") (pin "2") (pinfunction "2_2") (pintype "passive"))
      (node (ref "R116") (pin "1") (pinfunction "1_1") (pintype "passive"))
      (node (ref "SW6") (pin "6") (pinfunction "6_6") (pintype "passive"))
    )
    (net (code "18") (name "/DIR_CTRL14") (class "Default")
      (node (ref "IC25") (pin "11") (pinfunction "P6_11") (pintype "bidirectional"))
      (node (ref "R109") (pin "2") (pinfunction "2_2") (pintype "passive"))
      (node (ref "R118") (pin "1") (pinfunction "1_1") (pintype "passive"))
      (node (ref "SW6") (pin "7") (pinfunction "7_7") (pintype "passive"))
    )
    (net (code "19") (name "/DIR_CTRL15") (class "Default")
      (node (ref "IC25") (pin "12") (pinfunction "P7_12") (pintype "bidirectional"))
      (node (ref "R111") (pin "2") (pinfunction "2_2") (pintype "passive"))
      (node (ref "R120") (pin "1") (pinfunction "1_1") (pintype "passive"))
      (node (ref "SW6") (pin "8") (pinfunction "8_8") (pintype "passive"))
    )
    (net (code "22") (name "/I2C1_SCL") (class "Default")
      (node (ref "B2") (pin "1") (pinfunction "1_1") (pintype "bidirectional"))
      (node (ref "D9") (pin "6") (pinfunction "I/O4_6") (pintype "bidirectional"))
      (node (ref "IC23") (pin "14") (pinfunction "SCL_14") (pintype "input"))
      (node (ref "IC24") (pin "6") (pinfunction "SCL_6") (pintype "input"))
    )
    (net (code "23") (name "/I2C1_SDA") (class "Default")
      (node (ref "B6") (pin "1") (pinfunction "1_1") (pintype "bidirectional"))
      (node (ref "D9") (pin "1") (pinfunction "I/O1_1") (pintype "bidirectional"))
      (node (ref "IC23") (pin "15") (pinfunction "SDA_15") (pintype "bidirectional"))
      (node (ref "IC24") (pin "5") (pinfunction "SDA_5") (pintype "bidirectional"))
    )
    (net (code "24") (name "/I2C2_SCL") (class "Default")
      (node (ref "B4") (pin "1") (pinfunction "1_1") (pintype "bidirectional"))
      (node (ref "D10") (pin "6") (pinfunction "I/O4_6") (pintype "bidirectional"))
      (node (ref "IC25") (pin "14") (pinfunction "SCL_14") (pintype "input"))
      (node (ref "IC26") (pin "6") (pinfunction "SCL_6") (pintype "input"))
    )
    (net (code "25") (name "/I2C2_SDA") (class "Default")
      (node (ref "B3") (pin "1") (pinfunction "1_1") (pintype "bidirectional"))
      (node (ref "D10") (pin "1") (pinfunction "I/O1_1") (pintype "bidirectional"))
      (node (ref "IC25") (pin "15") (pinfunction "SDA_15") (pintype "bidirectional"))
      (node (ref "IC26") (pin "5") (pinfunction "SDA_5") (pintype "bidirectional"))
    )
    (net (code "58") (name "/LVDSC0_N") (class "Default")
      (node (ref "D1") (pin "3") (pinfunction "I/O2_3") (pintype "bidirectional"))
      (node (ref "J15") (pin "2D") (pinfunction "2_2D") (pintype "bidirectional"))
    )
    (net (code "59") (name "/LVDSC0_P") (class "Default")
      (node (ref "D1") (pin "1") (pinfunction "I/O1_1") (pintype "bidirectional"))
      (node (ref "J15") (pin "1D") (pinfunction "1_1D") (pintype "bidirectional"))
    )
    (net (code "60") (name "/LVDSC1_N") (class "Default")
      (node (ref "D2") (pin "3") (pinfunction "I/O2_3") (pintype "bidirectional"))
      (node (ref "J15") (pin "5D") (pinfunction "5_5D") (pintype "bidirectional"))
    )
    (net (code "61") (name "/LVDSC1_P") (class "Default")
      (node (ref "D2") (pin "1") (pinfunction "I/O1_1") (pintype "bidirectional"))
      (node (ref "J15") (pin "4D") (pinfunction "4_4D") (pintype "bidirectional"))
    )
    (net (code "62") (name "/LVDSC2_N") (class "Default")
      (node (ref "D1") (pin "4") (pinfunction "I/O3_4") (pintype "bidirectional"))
      (node (ref "J15") (pin "6D") (pinfunction "6_6D") (pintype "bidirectional"))
    )
    (net (code "63") (name "/LVDSC2_P") (class "Default")
      (node (ref "D1") (pin "6") (pinfunction "I/O4_6") (pintype "bidirectional"))
      (node (ref "J15") (pin "3D") (pinfunction "3_3D") (pintype "bidirectional"))
    )
    (net (code "64") (name "/LVDSC3_N") (class "Default")
      (node (ref "D2") (pin "4") (pinfunction "I/O3_4") (pintype "bidirectional"))
      (node (ref "J15") (pin "8D") (pinfunction "8_8D") (pintype "bidirectional"))
    )
    (net (code "65") (name "/LVDSC3_P") (class "Default")
      (node (ref "D2") (pin "6") (pinfunction "I/O4_6") (pintype "bidirectional"))
      (node (ref "J15") (pin "7D") (pinfunction "7_7D") (pintype "bidirectional"))
    )
    (net (code "66") (name "/LVDSC4_N") (class "Default")
      (node (ref "D3") (pin "1") (pinfunction "I/O1_1") (pintype "bidirectional"))
      (node (ref "J15") (pin "2C") (pinfunction "2_2C") (pintype "bidirectional"))
    )
    (net (code "67") (name "/LVDSC4_P") (class "Default")
      (node (ref "D3") (pin "3") (pinfunction "I/O2_3") (pintype "bidirectional"))
      (node (ref "J15") (pin "1C") (pinfunction "1_1C") (pintype "bidirectional"))
    )
    (net (code "68") (name "/LVDSC5_N") (class "Default")
      (node (ref "D4") (pin "1") (pinfunction "I/O1_1") (pintype "bidirectional"))
      (node (ref "J15") (pin "5C") (pinfunction "5_5C") (pintype "bidirectional"))
    )
    (net (code "69") (name "/LVDSC5_P") (class "Default")
      (node (ref "D4") (pin "3") (pinfunction "I/O2_3") (pintype "bidirectional"))
      (node (ref "J15") (pin "4C") (pinfunction "4_4C") (pintype "bidirectional"))
    )
    (net (code "70") (name "/LVDSC6_N") (class "Default")
      (node (ref "D3") (pin "4") (pinfunction "I/O3_4") (pintype "bidirectional"))
      (node (ref "J15") (pin "6C") (pinfunction "6_6C") (pintype "bidirectional"))
    )
    (net (code "71") (name "/LVDSC6_P") (class "Default")
      (node (ref "D3") (pin "6") (pinfunction "I/O4_6") (pintype "bidirectional"))
      (node (ref "J15") (pin "3C") (pinfunction "3_3C") (pintype "bidirectional"))
    )
    (net (code "72") (name "/LVDSC7_N") (class "Default")
      (node (ref "D4") (pin "4") (pinfunction "I/O3_4") (pintype "bidirectional"))
      (node (ref "J15") (pin "8C") (pinfunction "8_8C") (pintype "bidirectional"))
    )
    (net (code "73") (name "/LVDSC7_P") (class "Default")
      (node (ref "D4") (pin "6") (pinfunction "I/O4_6") (pintype "bidirectional"))
      (node (ref "J15") (pin "7C") (pinfunction "7_7C") (pintype "bidirectional"))
    )
    (net (code "74") (name "/LVDSC8_N") (class "Default")
      (node (ref "D5") (pin "3") (pinfunction "I/O2_3") (pintype "bidirectional"))
      (node (ref "J15") (pin "2B") (pinfunction "2_2B") (pintype "bidirectional"))
    )
    (net (code "75") (name "/LVDSC8_P") (class "Default")
      (node (ref "D5") (pin "1") (pinfunction "I/O1_1") (pintype "bidirectional"))
      (node (ref "J15") (pin "1B") (pinfunction "1_1B") (pintype "bidirectional"))
    )
    (net (code "76") (name "/LVDSC9_N") (class "Default")
      (node (ref "D6") (pin "3") (pinfunction "I/O2_3") (pintype "bidirectional"))
      (node (ref "J15") (pin "5B") (pinfunction "5_5B") (pintype "bidirectional"))
    )
    (net (code "77") (name "/LVDSC9_P") (class "Default")
      (node (ref "D6") (pin "1") (pinfunction "I/O1_1") (pintype "bidirectional"))
      (node (ref "J15") (pin "4B") (pinfunction "4_4B") (pintype "bidirectional"))
    )
    (net (code "78") (name "/LVDSC10_N") (class "Default")
      (node (ref "D5") (pin "4") (pinfunction "I/O3_4") (pintype "bidirectional"))
      (node (ref "J15") (pin "6B") (pinfunction "6_6B") (pintype "bidirectional"))
    )
    (net (code "79") (name "/LVDSC10_P") (class "Default")
      (node (ref "D5") (pin "6") (pinfunction "I/O4_6") (pintype "bidirectional"))
      (node (ref "J15") (pin "3B") (pinfunction "3_3B") (pintype "bidirectional"))
    )
    (net (code "80") (name "/LVDSC11_N") (class "Default")
      (node (ref "D6") (pin "4") (pinfunction "I/O3_4") (pintype "bidirectional"))
      (node (ref "J15") (pin "8B") (pinfunction "8_8B") (pintype "bidirectional"))
    )
    (net (code "81") (name "/LVDSC11_P") (class "Default")
      (node (ref "D6") (pin "6") (pinfunction "I/O4_6") (pintype "bidirectional"))
      (node (ref "J15") (pin "7B") (pinfunction "7_7B") (pintype "bidirectional"))
    )
    (net (code "82") (name "/LVDSC12_N") (class "Default")
      (node (ref "D7") (pin "3") (pinfunction "I/O2_3") (pintype "bidirectional"))
      (node (ref "J15") (pin "2A") (pinfunction "2_2A") (pintype "bidirectional"))
    )
    (net (code "83") (name "/LVDSC12_P") (class "Default")
      (node (ref "D7") (pin "1") (pinfunction "I/O1_1") (pintype "bidirectional"))
      (node (ref "J15") (pin "1A") (pinfunction "1_1A") (pintype "bidirectional"))
    )
    (net (code "84") (name "/LVDSC13_N") (class "Default")
      (node (ref "D8") (pin "3") (pinfunction "I/O2_3") (pintype "bidirectional"))
      (node (ref "J15") (pin "5A") (pinfunction "5_5A") (pintype "bidirectional"))
    )
    (net (code "85") (name "/LVDSC13_P") (class "Default")
      (node (ref "D8") (pin "1") (pinfunction "I/O1_1") (pintype "bidirectional"))
      (node (ref "J15") (pin "4A") (pinfunction "4_4A") (pintype "bidirectional"))
    )
    (net (code "86") (name "/LVDSC14_N") (class "Default")
      (node (ref "D7") (pin "4") (pinfunction "I/O3_4") (pintype "bidirectional"))
      (node (ref "J15") (pin "6A") (pinfunction "6_6A") (pintype "bidirectional"))
    )
    (net (code "87") (name "/LVDSC14_P") (class "Default")
      (node (ref "D7") (pin "6") (pinfunction "I/O4_6") (pintype "bidirectional"))
      (node (ref "J15") (pin "3A") (pinfunction "3_3A") (pintype "bidirectional"))
    )
    (net (code "88") (name "/LVDSC15_N") (class "Default")
      (node (ref "D8") (pin "4") (pinfunction "I/O3_4") (pintype "bidirectional"))
      (node (ref "J15") (pin "8A") (pinfunction "8_8A") (pintype "bidirectional"))
    )
    (net (code "89") (name "/LVDSC15_P") (class "Default")
      (node (ref "D8") (pin "6") (pinfunction "I/O4_6") (pintype "bidirectional"))
      (node (ref "J15") (pin "7A") (pinfunction "7_7A") (pintype "bidirectional"))
    )
    (net (code "91") (name "GND") (class "Default")
      (node (ref "B5") (pin "1") (pinfunction "1_1") (pintype "bidirectional"))
      (node (ref "B7") (pin "1") (pinfunction "1_1") (pintype "bidirectional"))
      (node (ref "B9") (pin "1") (pinfunction "1_1") (pintype "bidirectional"))
      (node (ref "C57") (pin "1") (pinfunction "1_1") (pintype "passive"))
      (node (ref "C58") (pin "1") (pinfunction "1_1") (pintype "passive"))
      (node (ref "C63") (pin "1") (pinfunction "1_1") (pintype "passive"))
      (node (ref "C64") (pin "1") (pinfunction "1_1") (pintype "passive"))
      (node (ref "D1") (pin "2") (pinfunction "GND_2") (pintype "power_in"))
      (node (ref "D10") (pin "2") (pinfunction "GND_2") (pintype "power_in"))
      (node (ref "D2") (pin "2") (pinfunction "GND_2") (pintype "power_in"))
      (node (ref "D3") (pin "2") (pinfunction "GND_2") (pintype "power_in"))
      (node (ref "D4") (pin "2") (pinfunction "GND_2") (pintype "power_in"))
      (node (ref "D5") (pin "2") (pinfunction "GND_2") (pintype "power_in"))
      (node (ref "D6") (pin "2") (pinfunction "GND_2") (pintype "power_in"))
      (node (ref "D7") (pin "2") (pinfunction "GND_2") (pintype "power_in"))
      (node (ref "D8") (pin "2") (pinfunction "GND_2") (pintype "power_in"))
      (node (ref "D9") (pin "2") (pinfunction "GND_2") (pintype "power_in"))
      (node (ref "IC23") (pin "1") (pinfunction "A0_1") (pintype "input"))
      (node (ref "IC23") (pin "8") (pinfunction "GND_8") (pintype "power_in"))
      (node (ref "IC24") (pin "1") (pinfunction "A0_1") (pintype "input"))
      (node (ref "IC24") (pin "2") (pinfunction "A1_2") (pintype "input"))
      (node (ref "IC24") (pin "3") (pinfunction "A2_3") (pintype "input"))
      (node (ref "IC24") (pin "4") (pinfunction "VSS_4") (pintype "power_in"))
      (node (ref "IC25") (pin "1") (pinfunction "A0_1") (pintype "input"))
      (node (ref "IC25") (pin "8") (pinfunction "GND_8") (pintype "power_in"))
      (node (ref "IC26") (pin "2") (pinfunction "A1_2") (pintype "input"))
      (node (ref "IC26") (pin "3") (pinfunction "A2_3") (pintype "input"))
      (node (ref "IC26") (pin "4") (pinfunction "VSS_4") (pintype "power_in"))
      (node (ref "J15") (pin "SH") (pinfunction "1_SH") (pintype "passive"))
      (node (ref "R68") (pin "2") (pinfunction "2_2") (pintype "passive"))
      (node (ref "SW5") (pin "10") (pinfunction "10_10") (pintype "passive"))
      (node (ref "SW5") (pin "11") (pinfunction "11_11") (pintype "passive"))
      (node (ref "SW5") (pin "12") (pinfunction "12_12") (pintype "passive"))
      (node (ref "SW5") (pin "13") (pinfunction "13_13") (pintype "passive"))
      (node (ref "SW5") (pin "14") (pinfunction "14_14") (pintype "passive"))
      (node (ref "SW5") (pin "15") (pinfunction "15_15") (pintype "passive"))
      (node (ref "SW5") (pin "16") (pinfunction "16_16") (pintype "passive"))
      (node (ref "SW5") (pin "9") (pinfunction "9_9") (pintype "passive"))
      (node (ref "SW6") (pin "10") (pinfunction "10_10") (pintype "passive"))
      (node (ref "SW6") (pin "11") (pinfunction "11_11") (pintype "passive"))
      (node (ref "SW6") (pin "12") (pinfunction "12_12") (pintype "passive"))
      (node (ref "SW6") (pin "13") (pinfunction "13_13") (pintype "passive"))
      (node (ref "SW6") (pin "14") (pinfunction "14_14") (pintype "passive"))
      (node (ref "SW6") (pin "15") (pinfunction "15_15") (pintype "passive"))
      (node (ref "SW6") (pin "16") (pinfunction "16_16") (pintype "passive"))
      (node (ref "SW6") (pin "9") (pinfunction "9_9") (pintype "passive"))
    )
    (net (code "92") (name "Net-(IC26-A0)") (class "Default")
      (node (ref "IC26") (pin "1") (pinfunction "A0_1") (pintype "input"))
      (node (ref "R61") (pin "1") (pinfunction "1_1") (pintype "passive"))
      (node (ref "R68") (pin "1") (pinfunction "1_1") (pintype "passive"))
    )
    (net (code "93") (name "Net-(LD1A-C)") (class "Default")
      (node (ref "LD1") (pin "1") (pinfunction "C_1") (pintype "passive"))
      (node (ref "R89") (pin "1") (pinfunction "1_1") (pintype "passive"))
    )
    (net (code "94") (name "Net-(LD1B-C)") (class "Default")
      (node (ref "LD1") (pin "3") (pinfunction "C_3") (pintype "passive"))
      (node (ref "R91") (pin "1") (pinfunction "1_1") (pintype "passive"))
    )
    (net (code "95") (name "Net-(LD1C-C)") (class "Default")
      (node (ref "LD1") (pin "5") (pinfunction "C_5") (pintype "passive"))
      (node (ref "R93") (pin "1") (pinfunction "1_1") (pintype "passive"))
    )
    (net (code "96") (name "Net-(LD1D-C)") (class "Default")
      (node (ref "LD1") (pin "7") (pinfunction "C_7") (pintype "passive"))
      (node (ref "R95") (pin "1") (pinfunction "1_1") (pintype "passive"))
    )
    (net (code "97") (name "Net-(LD2A-C)") (class "Default")
      (node (ref "LD2") (pin "1") (pinfunction "C_1") (pintype "passive"))
      (node (ref "R97") (pin "1") (pinfunction "1_1") (pintype "passive"))
    )
    (net (code "98") (name "Net-(LD2B-C)") (class "Default")
      (node (ref "LD2") (pin "3") (pinfunction "C_3") (pintype "passive"))
      (node (ref "R99") (pin "1") (pinfunction "1_1") (pintype "passive"))
    )
    (net (code "99") (name "Net-(LD2C-C)") (class "Default")
      (node (ref "LD2") (pin "5") (pinfunction "C_5") (pintype "passive"))
      (node (ref "R101") (pin "1") (pinfunction "1_1") (pintype "passive"))
    )
    (net (code "100") (name "Net-(LD2D-C)") (class "Default")
      (node (ref "LD2") (pin "7") (pinfunction "C_7") (pintype "passive"))
      (node (ref "R103") (pin "1") (pinfunction "1_1") (pintype "passive"))
    )
    (net (code "101") (name "Net-(LD3A-C)") (class "Default")
      (node (ref "LD3") (pin "1") (pinfunction "C_1") (pintype "passive"))
      (node (ref "R105") (pin "1") (pinfunction "1_1") (pintype "passive"))
    )
    (net (code "102") (name "Net-(LD3B-C)") (class "Default")
      (node (ref "LD3") (pin "3") (pinfunction "C_3") (pintype "passive"))
      (node (ref "R107") (pin "1") (pinfunction "1_1") (pintype "passive"))
    )
    (net (code "103") (name "Net-(LD3C-C)") (class "Default")
      (node (ref "LD3") (pin "5") (pinfunction "C_5") (pintype "passive"))
      (node (ref "R109") (pin "1") (pinfunction "1_1") (pintype "passive"))
    )
    (net (code "104") (name "Net-(LD3D-C)") (class "Default")
      (node (ref "LD3") (pin "7") (pinfunction "C_7") (pintype "passive"))
      (node (ref "R111") (pin "1") (pinfunction "1_1") (pintype "passive"))
    )
    (net (code "105") (name "Net-(LD4A-C)") (class "Default")
      (node (ref "LD4") (pin "1") (pinfunction "C_1") (pintype "passive"))
      (node (ref "R113") (pin "1") (pinfunction "1_1") (pintype "passive"))
    )
    (net (code "106") (name "Net-(LD4B-C)") (class "Default")
      (node (ref "LD4") (pin "3") (pinfunction "C_3") (pintype "passive"))
      (node (ref "R115") (pin "1") (pinfunction "1_1") (pintype "passive"))
    )
    (net (code "107") (name "Net-(LD4C-C)") (class "Default")
      (node (ref "LD4") (pin "5") (pinfunction "C_5") (pintype "passive"))
      (node (ref "R117") (pin "1") (pinfunction "1_1") (pintype "passive"))
    )
    (net (code "108") (name "Net-(LD4D-C)") (class "Default")
      (node (ref "LD4") (pin "7") (pinfunction "C_7") (pintype "passive"))
      (node (ref "R119") (pin "1") (pinfunction "1_1") (pintype "passive"))
    )
    (net (code "109") (name "P3V3") (class "Default")
      (node (ref "B10") (pin "1") (pinfunction "1_1") (pintype "bidirectional"))
      (node (ref "D1") (pin "5") (pinfunction "VBUS_5") (pintype "power_in"))
      (node (ref "D2") (pin "5") (pinfunction "VBUS_5") (pintype "power_in"))
      (node (ref "D3") (pin "5") (pinfunction "VBUS_5") (pintype "power_in"))
      (node (ref "D4") (pin "5") (pinfunction "VBUS_5") (pintype "power_in"))
      (node (ref "D5") (pin "5") (pinfunction "VBUS_5") (pintype "power_in"))
      (node (ref "D6") (pin "5") (pinfunction "VBUS_5") (pintype "power_in"))
      (node (ref "D7") (pin "5") (pinfunction "VBUS_5") (pintype "power_in"))
      (node (ref "D8") (pin "5") (pinfunction "VBUS_5") (pintype "power_in"))
      (node (ref "LD1") (pin "2") (pinfunction "A_2") (pintype "passive"))
      (node (ref "LD1") (pin "4") (pinfunction "A_4") (pintype "passive"))
      (node (ref "LD1") (pin "6") (pinfunction "A_6") (pintype "passive"))
      (node (ref "LD1") (pin "8") (pinfunction "A_8") (pintype "passive"))
      (node (ref "LD2") (pin "2") (pinfunction "A_2") (pintype "passive"))
      (node (ref "LD2") (pin "4") (pinfunction "A_4") (pintype "passive"))
      (node (ref "LD2") (pin "6") (pinfunction "A_6") (pintype "passive"))
      (node (ref "LD2") (pin "8") (pinfunction "A_8") (pintype "passive"))
      (node (ref "LD3") (pin "2") (pinfunction "A_2") (pintype "passive"))
      (node (ref "LD3") (pin "4") (pinfunction "A_4") (pintype "passive"))
      (node (ref "LD3") (pin "6") (pinfunction "A_6") (pintype "passive"))
      (node (ref "LD3") (pin "8") (pinfunction "A_8") (pintype "passive"))
      (node (ref "LD4") (pin "2") (pinfunction "A_2") (pintype "passive"))
      (node (ref "LD4") (pin "4") (pinfunction "A_4") (pintype "passive"))
      (node (ref "LD4") (pin "6") (pinfunction "A_6") (pintype "passive"))
      (node (ref "LD4") (pin "8") (pinfunction "A_8") (pintype "passive"))
      (node (ref "R100") (pin "2") (pinfunction "2_2") (pintype "passive"))
      (node (ref "R102") (pin "2") (pinfunction "2_2") (pintype "passive"))
      (node (ref "R104") (pin "2") (pinfunction "2_2") (pintype "passive"))
      (node (ref "R106") (pin "2") (pinfunction "2_2") (pintype "passive"))
      (node (ref "R108") (pin "2") (pinfunction "2_2") (pintype "passive"))
      (node (ref "R110") (pin "2") (pinfunction "2_2") (pintype "passive"))
      (node (ref "R112") (pin "2") (pinfunction "2_2") (pintype "passive"))
      (node (ref "R114") (pin "2") (pinfunction "2_2") (pintype "passive"))
      (node (ref "R116") (pin "2") (pinfunction "2_2") (pintype "passive"))
      (node (ref "R118") (pin "2") (pinfunction "2_2") (pintype "passive"))
      (node (ref "R120") (pin "2") (pinfunction "2_2") (pintype "passive"))
      (node (ref "R90") (pin "2") (pinfunction "2_2") (pintype "passive"))
      (node (ref "R92") (pin "2") (pinfunction "2_2") (pintype "passive"))
      (node (ref "R94") (pin "2") (pinfunction "2_2") (pintype "passive"))
      (node (ref "R96") (pin "2") (pinfunction "2_2") (pintype "passive"))
      (node (ref "R98") (pin "2") (pinfunction "2_2") (pintype "passive"))
    )
    (net (code "110") (name "P3V3_MP1") (class "Default")
      (node (ref "B8") (pin "1") (pinfunction "1_1") (pintype "bidirectional"))
      (node (ref "C57") (pin "2") (pinfunction "2_2") (pintype "passive"))
      (node (ref "C58") (pin "2") (pinfunction "2_2") (pintype "passive"))
      (node (ref "D9") (pin "5") (pinfunction "VBUS_5") (pintype "power_in"))
      (node (ref "IC23") (pin "16") (pinfunction "VCC_16") (pintype "bidirectional"))
      (node (ref "IC23") (pin "2") (pinfunction "A1_2") (pintype "input"))
      (node (ref "IC23") (pin "3") (pinfunction "A2_3") (pintype "input"))
      (node (ref "IC24") (pin "8") (pinfunction "VCC_8") (pintype "power_in"))
    )
    (net (code "111") (name "P3V3_MP2") (class "Default")
      (node (ref "B1") (pin "1") (pinfunction "1_1") (pintype "bidirectional"))
      (node (ref "C63") (pin "2") (pinfunction "2_2") (pintype "passive"))
      (node (ref "C64") (pin "2") (pinfunction "2_2") (pintype "passive"))
      (node (ref "D10") (pin "5") (pinfunction "VBUS_5") (pintype "power_in"))
      (node (ref "IC25") (pin "16") (pinfunction "VCC_16") (pintype "bidirectional"))
      (node (ref "IC25") (pin "2") (pinfunction "A1_2") (pintype "input"))
      (node (ref "IC25") (pin "3") (pinfunction "A2_3") (pintype "input"))
      (node (ref "IC26") (pin "8") (pinfunction "VCC_8") (pintype "power_in"))
      (node (ref "R61") (pin "2") (pinfunction "2_2") (pintype "passive"))
    )
    (net (code "112") (name "P12V0") (class "Default")
      (node (ref "B11") (pin "1") (pinfunction "1_1") (pintype "bidirectional"))
    )
    (net (code "113") (name "unconnected-(D9-I{slash}O2-Pad3)") (class "Default")
      (node (ref "D9") (pin "3") (pinfunction "I/O2_3") (pintype "bidirectional"))
    )
    (net (code "114") (name "unconnected-(D9-I{slash}O3-Pad4)") (class "Default")
      (node (ref "D9") (pin "4") (pinfunction "I/O3_4") (pintype "bidirectional"))
    )
    (net (code "115") (name "unconnected-(D10-I{slash}O2-Pad3)") (class "Default")
      (node (ref "D10") (pin "3") (pinfunction "I/O2_3") (pintype "bidirectional"))
    )
    (net (code "116") (name "unconnected-(D10-I{slash}O3-Pad4)") (class "Default")
      (node (ref "D10") (pin "4") (pinfunction "I/O3_4") (pintype "bidirectional"))
    )
    (net (code "117") (name "unconnected-(IC23-~{INT}-Pad13)") (class "Default")
      (node (ref "IC23") (pin "13") (pinfunction "~{INT}_13") (pintype "output"))
    )
    (net (code "118") (name "unconnected-(IC24-NC-Pad7)") (class "Default")
      (node (ref "IC24") (pin "7") (pinfunction "NC_7") (pintype "passive"))
    )
    (net (code "119") (name "unconnected-(IC25-~{INT}-Pad13)") (class "Default")
      (node (ref "IC25") (pin "13") (pinfunction "~{INT}_13") (pintype "output"))
    )
    (net (code "120") (name "unconnected-(IC26-NC-Pad7)") (class "Default")
      (node (ref "IC26") (pin "7") (pinfunction "NC_7") (pintype "passive"))
    )
  )
)
